# Power.net
KiCad netlist of a schematic drawn in Altium Designer
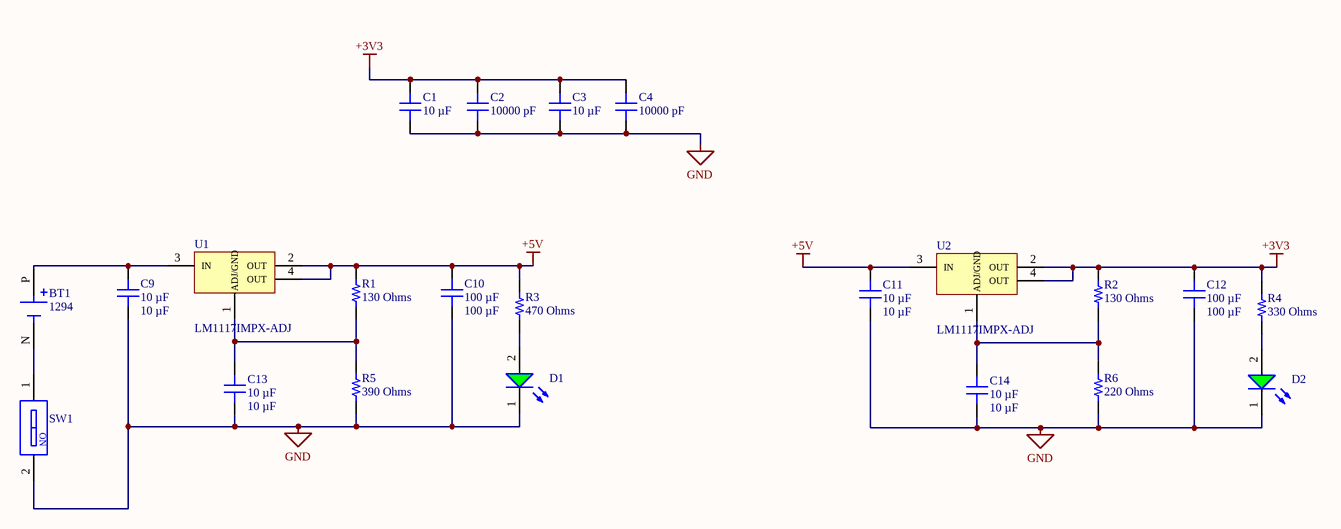
[diagram p0: Power.SchDoc]

(export (version "E")
  (design (tool "Eeschema 10.0.6"))
  (components
    (comp (ref "BT1")
      (value "1294")
      (footprint "BAT_1294")
      (description "9V battery holder")
      (libsource (lib "Schlib1") (part "Bat-1294"))
    )
    (comp (ref "C1")
      (value "10 µF")
      (footprint "CAP 0805_2012")
      (description "CAP CER 10UF 25V X5R 0805")
      (fields (field (name "PART NUMBER") "C0805C106K3PAC7800") (field (name "MANUFACTURER") "KEMET"))
      (libsource (lib "Celestial Altium Library - altium_library (2)") (part "Capacitor"))
    )
    (comp (ref "C2")
      (value "10000 pF")
      (footprint "CAP 0805_2012")
      (description "CAP CER 0805 10NF 25V C0G 5%")
      (fields (field (name "PART NUMBER") "C0805C103J3GECAUTO") (field (name "MANUFACTURER") "KEMET"))
      (libsource (lib "Celestial Altium Library - altium_library (2)") (part "Capacitor"))
    )
    (comp (ref "C3")
      (value "10 µF")
      (footprint "CAP 0805_2012")
      (description "CAP CER 10UF 25V X5R 0805")
      (fields (field (name "PART NUMBER") "C0805C106K3PAC7800") (field (name "MANUFACTURER") "KEMET"))
      (libsource (lib "Celestial Altium Library - altium_library (2)") (part "Capacitor"))
    )
    (comp (ref "C4")
      (value "10000 pF")
      (footprint "CAP 0805_2012")
      (description "CAP CER 0805 10NF 25V C0G 5%")
      (fields (field (name "PART NUMBER") "C0805C103J3GECAUTO") (field (name "MANUFACTURER") "KEMET"))
      (libsource (lib "Celestial Altium Library - altium_library (2)") (part "Capacitor"))
    )
    (comp (ref "C9")
      (value "10 µF")
      (footprint "CAP 0805_2012")
      (description "CAP CER 10UF 10V X7S 0805")
      (fields (field (name "PART NUMBER") "CL21Y106KPQVPNE") (field (name "ALTIUM_VALUE") "10 µF"))
      (libsource (lib "Celestial Altium Library - altium_library (2)") (part "Capacitor"))
    )
    (comp (ref "C10")
      (value "100 µF")
      (footprint "CAP 0805_2012")
      (description "CAP CER 100UF 2.5V X5R 0805")
      (fields (field (name "PART NUMBER") "PMK212BBJ107MG-T") (field (name "ALTIUM_VALUE") "100 µF"))
      (libsource (lib "Celestial Altium Library - altium_library (2)") (part "Capacitor"))
    )
    (comp (ref "C11")
      (value "10 µF")
      (footprint "CAP 0805_2012")
      (description "CAP CER 10UF 10V X7S 0805")
      (fields (field (name "PART NUMBER") "CL21Y106KPQVPNE") (field (name "ALTIUM_VALUE") "10 µF"))
      (libsource (lib "Celestial Altium Library - altium_library (2)") (part "Capacitor"))
    )
    (comp (ref "C12")
      (value "100 µF")
      (footprint "CAP 0805_2012")
      (description "CAP CER 100UF 2.5V X5R 0805")
      (fields (field (name "PART NUMBER") "PMK212BBJ107MG-T") (field (name "ALTIUM_VALUE") "100 µF"))
      (libsource (lib "Celestial Altium Library - altium_library (2)") (part "Capacitor"))
    )
    (comp (ref "C13")
      (value "10 µF")
      (footprint "CAP 0805_2012")
      (description "CAP CER 10UF 10V X7S 0805")
      (fields (field (name "PART NUMBER") "CL21Y106KPQVPNE") (field (name "ALTIUM_VALUE") "10 µF"))
      (libsource (lib "Celestial Altium Library - altium_library (2)") (part "Capacitor"))
    )
    (comp (ref "C14")
      (value "10 µF")
      (footprint "CAP 0805_2012")
      (description "CAP CER 10UF 10V X7S 0805")
      (fields (field (name "PART NUMBER") "CL21Y106KPQVPNE") (field (name "ALTIUM_VALUE") "10 µF"))
      (libsource (lib "Celestial Altium Library - altium_library (2)") (part "Capacitor"))
    )
    (comp (ref "D1")
      (value "Green, 3.2V, 140°")
      (footprint "WL-SMCW_0805_150080xx75000")
      (description "WL-SMCW Mono-color Chip LED Waterclear, size 0805, Green, 3.2V, 140°")
      (fields
        (field (name "MANUFACTURER PART NUMBER") "150080GS75000")
        (field (name "MANUFACTURER") "Wurth Elektronik")
      )
      (libsource (lib "WE - Optoelectronic Components") (part "LED_Green_2A-1K"))
    )
    (comp (ref "D2")
      (value "Green, 3.2V, 140°")
      (footprint "WL-SMCW_0805_150080xx75000")
      (description "WL-SMCW Mono-color Chip LED Waterclear, size 0805, Green, 3.2V, 140°")
      (fields
        (field (name "MANUFACTURER PART NUMBER") "150080GS75000")
        (field (name "MANUFACTURER") "Wurth Elektronik")
      )
      (libsource (lib "WE - Optoelectronic Components") (part "LED_Green_2A-1K"))
    )
    (comp (ref "R1")
      (value "130 Ohms")
      (footprint "RES 0805_2012")
      (description "RES SMD 130 OHM 0.1% 1/4W 0805")
      (fields
        (field (name "PART NUMBER") "3-2176091-5")
        (field (name "MANUFACTURER") "TE Connectivity Passive Product")
      )
      (libsource (lib "Celestial Altium Library - altium_library (2)") (part "Resistor"))
    )
    (comp (ref "R2")
      (value "130 Ohms")
      (footprint "RES 0805_2012")
      (description "RES SMD 130 OHM 0.1% 1/4W 0805")
      (fields
        (field (name "PART NUMBER") "3-2176091-5")
        (field (name "MANUFACTURER") "TE Connectivity Passive Product")
      )
      (libsource (lib "Celestial Altium Library - altium_library (2)") (part "Resistor"))
    )
    (comp (ref "R3")
      (value "470 Ohms")
      (footprint "RES 0805_2012")
      (description "3430 A2 1% 470R 100PPM 1K RL")
      (fields
        (field (name "PART NUMBER") "3430A2F470RTDF")
        (field (name "MANUFACTURER") "TE Connectivity Passive Product")
      )
      (libsource (lib "Celestial Altium Library - altium_library (2)") (part "Resistor"))
    )
    (comp (ref "R4")
      (value "330 Ohms")
      (footprint "RES 0805_2012")
      (description "3430 A2 1% 330R 100PPM 1K RL")
      (fields
        (field (name "PART NUMBER") "3430A2F330RTDF")
        (field (name "MANUFACTURER") "TE Connectivity Passive Product")
      )
      (libsource (lib "Celestial Altium Library - altium_library (2)") (part "Resistor"))
    )
    (comp (ref "R5")
      (value "390 Ohms")
      (footprint "RES 0805_2012")
      (description "3430 A2 1% 390R 100PPM 1K RL")
      (fields
        (field (name "PART NUMBER") "3430A2F390RTDF")
        (field (name "MANUFACTURER") "TE Connectivity Passive Product")
      )
      (libsource (lib "Celestial Altium Library - altium_library (2)") (part "Resistor"))
    )
    (comp (ref "R6")
      (value "220 Ohms")
      (footprint "RES 0805_2012")
      (description "RES SMD 220 OHM 0.1% 1/10W 0805")
      (fields
        (field (name "PART NUMBER") "CPF0805B220RE1")
        (field (name "MANUFACTURER") "TE Connectivity Passive Product")
      )
      (libsource (lib "Celestial Altium Library - altium_library (2)") (part "Resistor"))
    )
    (comp (ref "SW1")
      (value "418121270801")
      (footprint "418121270801")
      (description "WS-DISV Small Compact SMT Dip Switch, Raised Actuator, pitch 2.54mm, 1p")
      (fields (field (name "MANUFACTURER") "Wurth Elektronik"))
      (libsource (lib "WE - Electromechanical Components") (part "DIP-1"))
    )
    (comp (ref "U1")
      (value "LM1117IMPX-ADJ")
      (footprint "SOT-223-4 M")
      (description "LDO Regulator Pos 3.3V 0.8A 4-Pin(3+Tab) SOT-223 T/R")
      (fields
        (field (name "MANUFACTURER") "Texas Instruments")
        (field (name "MANUFACTURER PART NUMBER") "LM1117IMPX-3.3")
      )
      (libsource (lib "Schlib1") (part "LM1117IMPX-ADJ"))
    )
    (comp (ref "U2")
      (value "LM1117IMPX-ADJ")
      (footprint "SOT-223-4 M")
      (description "LDO Regulator Pos 3.3V 0.8A 4-Pin(3+Tab) SOT-223 T/R")
      (fields
        (field (name "MANUFACTURER") "Texas Instruments")
        (field (name "MANUFACTURER PART NUMBER") "LM1117IMPX-3.3")
      )
      (libsource (lib "Schlib1") (part "LM1117IMPX-ADJ"))
    )
  )
  (nets
    (net (code "1") (name "+3V3") (class "Default")
      (node (ref "C1") (pin "1") (pinfunction "1_1") (pintype "passive"))
      (node (ref "C12") (pin "2") (pinfunction "2_2") (pintype "passive"))
      (node (ref "C2") (pin "2") (pinfunction "2_2") (pintype "passive"))
      (node (ref "C3") (pin "1") (pinfunction "1_1") (pintype "passive"))
      (node (ref "C4") (pin "2") (pinfunction "2_2") (pintype "passive"))
      (node (ref "R2") (pin "2") (pinfunction "2_2") (pintype "passive"))
      (node (ref "R4") (pin "2") (pinfunction "2_2") (pintype "passive"))
      (node (ref "U2") (pin "2") (pinfunction "OUT_2") (pintype "power_in"))
      (node (ref "U2") (pin "4") (pinfunction "OUT_4") (pintype "passive"))
    )
    (net (code "2") (name "+5V") (class "Default")
      (node (ref "C10") (pin "2") (pinfunction "2_2") (pintype "passive"))
      (node (ref "C11") (pin "2") (pinfunction "2_2") (pintype "passive"))
      (node (ref "R1") (pin "2") (pinfunction "2_2") (pintype "passive"))
      (node (ref "R3") (pin "2") (pinfunction "2_2") (pintype "passive"))
      (node (ref "U1") (pin "2") (pinfunction "OUT_2") (pintype "power_in"))
      (node (ref "U1") (pin "4") (pinfunction "OUT_4") (pintype "passive"))
      (node (ref "U2") (pin "3") (pinfunction "IN_3") (pintype "power_in"))
    )
    (net (code "3") (name "GND") (class "Default")
      (node (ref "C1") (pin "2") (pinfunction "2_2") (pintype "passive"))
      (node (ref "C10") (pin "1") (pinfunction "1_1") (pintype "passive"))
      (node (ref "C11") (pin "1") (pinfunction "1_1") (pintype "passive"))
      (node (ref "C12") (pin "1") (pinfunction "1_1") (pintype "passive"))
      (node (ref "C13") (pin "1") (pinfunction "1_1") (pintype "passive"))
      (node (ref "C14") (pin "1") (pinfunction "1_1") (pintype "passive"))
      (node (ref "C2") (pin "1") (pinfunction "1_1") (pintype "passive"))
      (node (ref "C3") (pin "2") (pinfunction "2_2") (pintype "passive"))
      (node (ref "C4") (pin "1") (pinfunction "1_1") (pintype "passive"))
      (node (ref "C9") (pin "1") (pinfunction "1_1") (pintype "passive"))
      (node (ref "D1") (pin "1") (pinfunction "K_1") (pintype "passive"))
      (node (ref "D2") (pin "1") (pinfunction "K_1") (pintype "passive"))
      (node (ref "R5") (pin "1") (pinfunction "1_1") (pintype "passive"))
      (node (ref "R6") (pin "1") (pinfunction "1_1") (pintype "passive"))
      (node (ref "SW1") (pin "2") (pinfunction "2_2") (pintype "passive"))
    )
    (net (code "4") (name "Net-(BT1-NEG)") (class "Default")
      (node (ref "BT1") (pin "N") (pinfunction "NEG_N") (pintype "passive"))
      (node (ref "SW1") (pin "1") (pinfunction "1_1") (pintype "passive"))
    )
    (net (code "5") (name "Net-(BT1-POS)") (class "Default")
      (node (ref "BT1") (pin "P") (pinfunction "POS_P") (pintype "passive"))
      (node (ref "C9") (pin "2") (pinfunction "2_2") (pintype "passive"))
      (node (ref "U1") (pin "3") (pinfunction "IN_3") (pintype "power_in"))
    )
    (net (code "6") (name "Net-(D1-A)") (class "Default")
      (node (ref "D1") (pin "2") (pinfunction "A_2") (pintype "passive"))
      (node (ref "R3") (pin "1") (pinfunction "1_1") (pintype "passive"))
    )
    (net (code "7") (name "Net-(D2-A)") (class "Default")
      (node (ref "D2") (pin "2") (pinfunction "A_2") (pintype "passive"))
      (node (ref "R4") (pin "1") (pinfunction "1_1") (pintype "passive"))
    )
    (net (code "8") (name "Net-(U1-ADJ{slash}GND)") (class "Default")
      (node (ref "C13") (pin "2") (pinfunction "2_2") (pintype "passive"))
      (node (ref "R1") (pin "1") (pinfunction "1_1") (pintype "passive"))
      (node (ref "R5") (pin "2") (pinfunction "2_2") (pintype "passive"))
      (node (ref "U1") (pin "1") (pinfunction "ADJ/GND_1") (pintype "power_in"))
    )
    (net (code "9") (name "Net-(U2-ADJ{slash}GND)") (class "Default")
      (node (ref "C14") (pin "2") (pinfunction "2_2") (pintype "passive"))
      (node (ref "R2") (pin "1") (pinfunction "1_1") (pintype "passive"))
      (node (ref "R6") (pin "2") (pinfunction "2_2") (pintype "passive"))
      (node (ref "U2") (pin "1") (pinfunction "ADJ/GND_1") (pintype "power_in"))
    )
  )
)
